# 03_SM_1222_DQ8_x_relay.net
KiCad netlist of a schematic drawn in Altium Designer
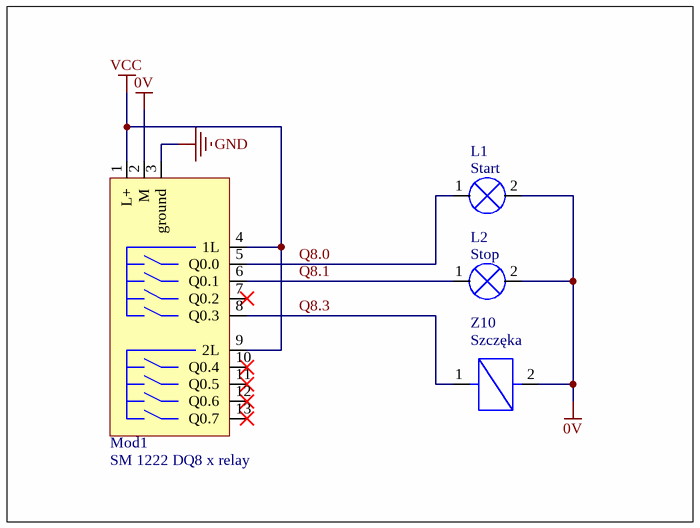
[diagram p0: [03] SM 1222 DQ8 x relay.SchDoc]

(export (version "E")
  (design (tool "Eeschema 10.0.6"))
  (components
    (comp (ref "L1") (value "Start") (libsource (lib "Schlib2") (part "Light")))
    (comp (ref "L2") (value "Stop") (libsource (lib "Schlib2") (part "Light")))
    (comp (ref "Mod1") (value "SM 1222 DQ8 x relay") (libsource (lib "Schlib2") (part "SM 1222 DQ8 x relay")))
    (comp (ref "Z10") (value "Szczęka") (libsource (lib "Schlib2") (part "Coil")))
  )
  (nets
    (net (code "1") (name "/Q8.0") (class "Default")
      (node (ref "L1") (pin "1") (pinfunction "*_1") (pintype "passive"))
      (node (ref "Mod1") (pin "5") (pinfunction "Q0.0_5") (pintype "passive"))
    )
    (net (code "2") (name "/Q8.1") (class "Default")
      (node (ref "L2") (pin "1") (pinfunction "*_1") (pintype "passive"))
      (node (ref "Mod1") (pin "6") (pinfunction "Q0.1_6") (pintype "passive"))
    )
    (net (code "3") (name "/Q8.3") (class "Default")
      (node (ref "Mod1") (pin "8") (pinfunction "Q0.3_8") (pintype "passive"))
      (node (ref "Z10") (pin "1") (pinfunction "*_1") (pintype "passive"))
    )
    (net (code "4") (name "0V") (class "Default")
      (node (ref "L1") (pin "2") (pinfunction "*_2") (pintype "passive"))
      (node (ref "L2") (pin "2") (pinfunction "*_2") (pintype "passive"))
      (node (ref "Mod1") (pin "2") (pinfunction "M_2") (pintype "passive"))
      (node (ref "Z10") (pin "2") (pinfunction "*_2") (pintype "passive"))
    )
    (net (code "5") (name "GND") (class "Default")
      (node (ref "Mod1") (pin "3") (pinfunction "ground_3") (pintype "passive"))
    )
    (net (code "6") (name "VCC") (class "Default")
      (node (ref "Mod1") (pin "1") (pinfunction "L+_1") (pintype "passive"))
      (node (ref "Mod1") (pin "4") (pinfunction "1L_4") (pintype "passive"))
      (node (ref "Mod1") (pin "9") (pinfunction "2L_9") (pintype "passive"))
    )
    (net (code "7") (name "unconnected-(Mod1-Q0.2-Pad7)") (class "Default")
      (node (ref "Mod1") (pin "7") (pinfunction "Q0.2_7") (pintype "passive+no_connect"))
    )
    (net (code "8") (name "unconnected-(Mod1-Q0.4-Pad10)") (class "Default")
      (node (ref "Mod1") (pin "10") (pinfunction "Q0.4_10") (pintype "passive+no_connect"))
    )
    (net (code "9") (name "unconnected-(Mod1-Q0.5-Pad11)") (class "Default")
      (node (ref "Mod1") (pin "11") (pinfunction "Q0.5_11") (pintype "passive+no_connect"))
    )
    (net (code "10") (name "unconnected-(Mod1-Q0.6-Pad12)") (class "Default")
      (node (ref "Mod1") (pin "12") (pinfunction "Q0.6_12") (pintype "passive+no_connect"))
    )
    (net (code "11") (name "unconnected-(Mod1-Q0.7-Pad13)") (class "Default")
      (node (ref "Mod1") (pin "13") (pinfunction "Q0.7_13") (pintype "passive+no_connect"))
    )
  )
)
